# shield_007.net
KiCad netlist of a schematic drawn in EAGLE
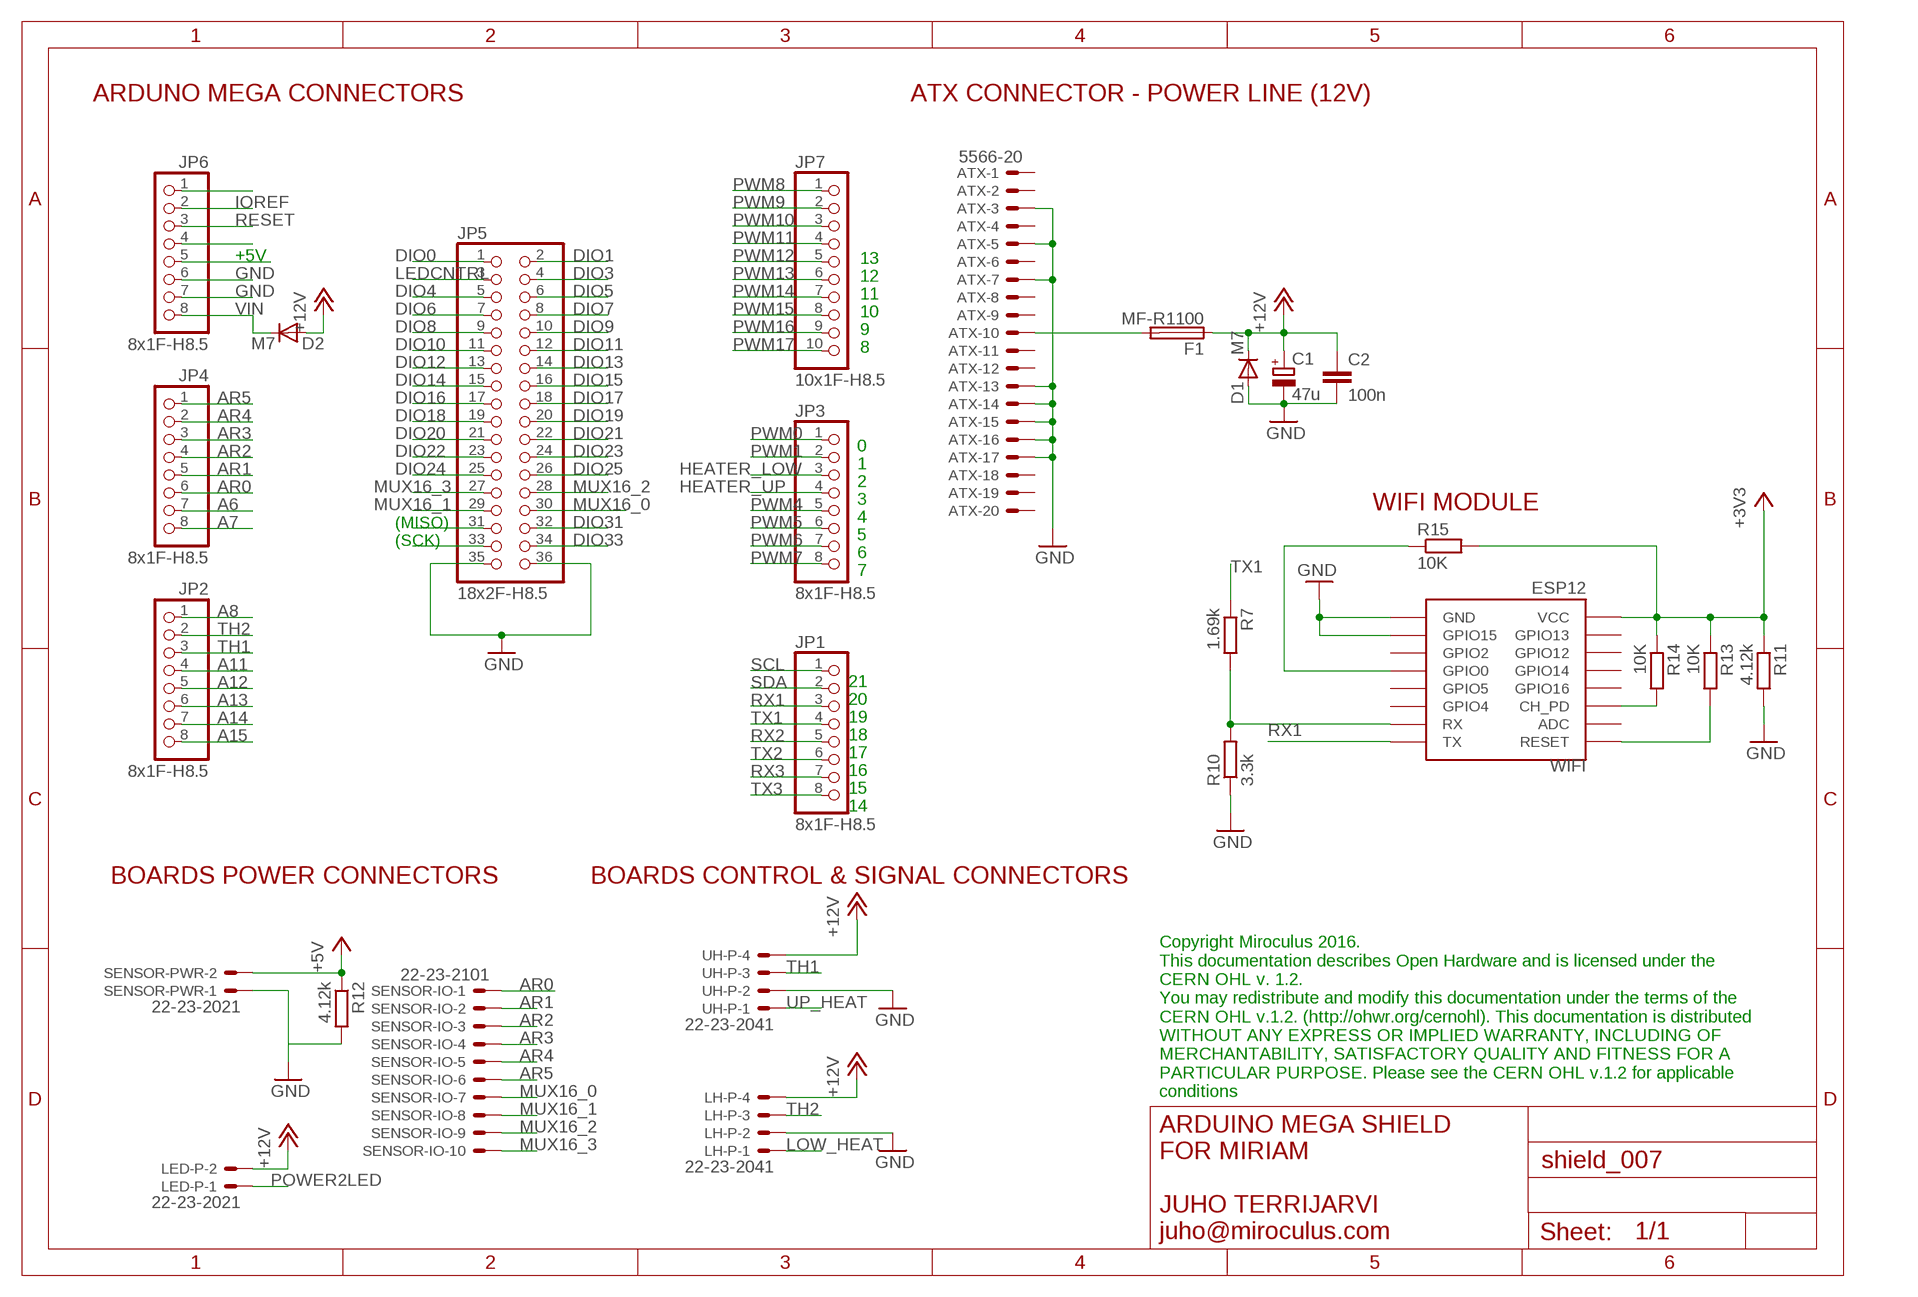
[diagram p0: schematic, sheet 1, part 1 of 2]
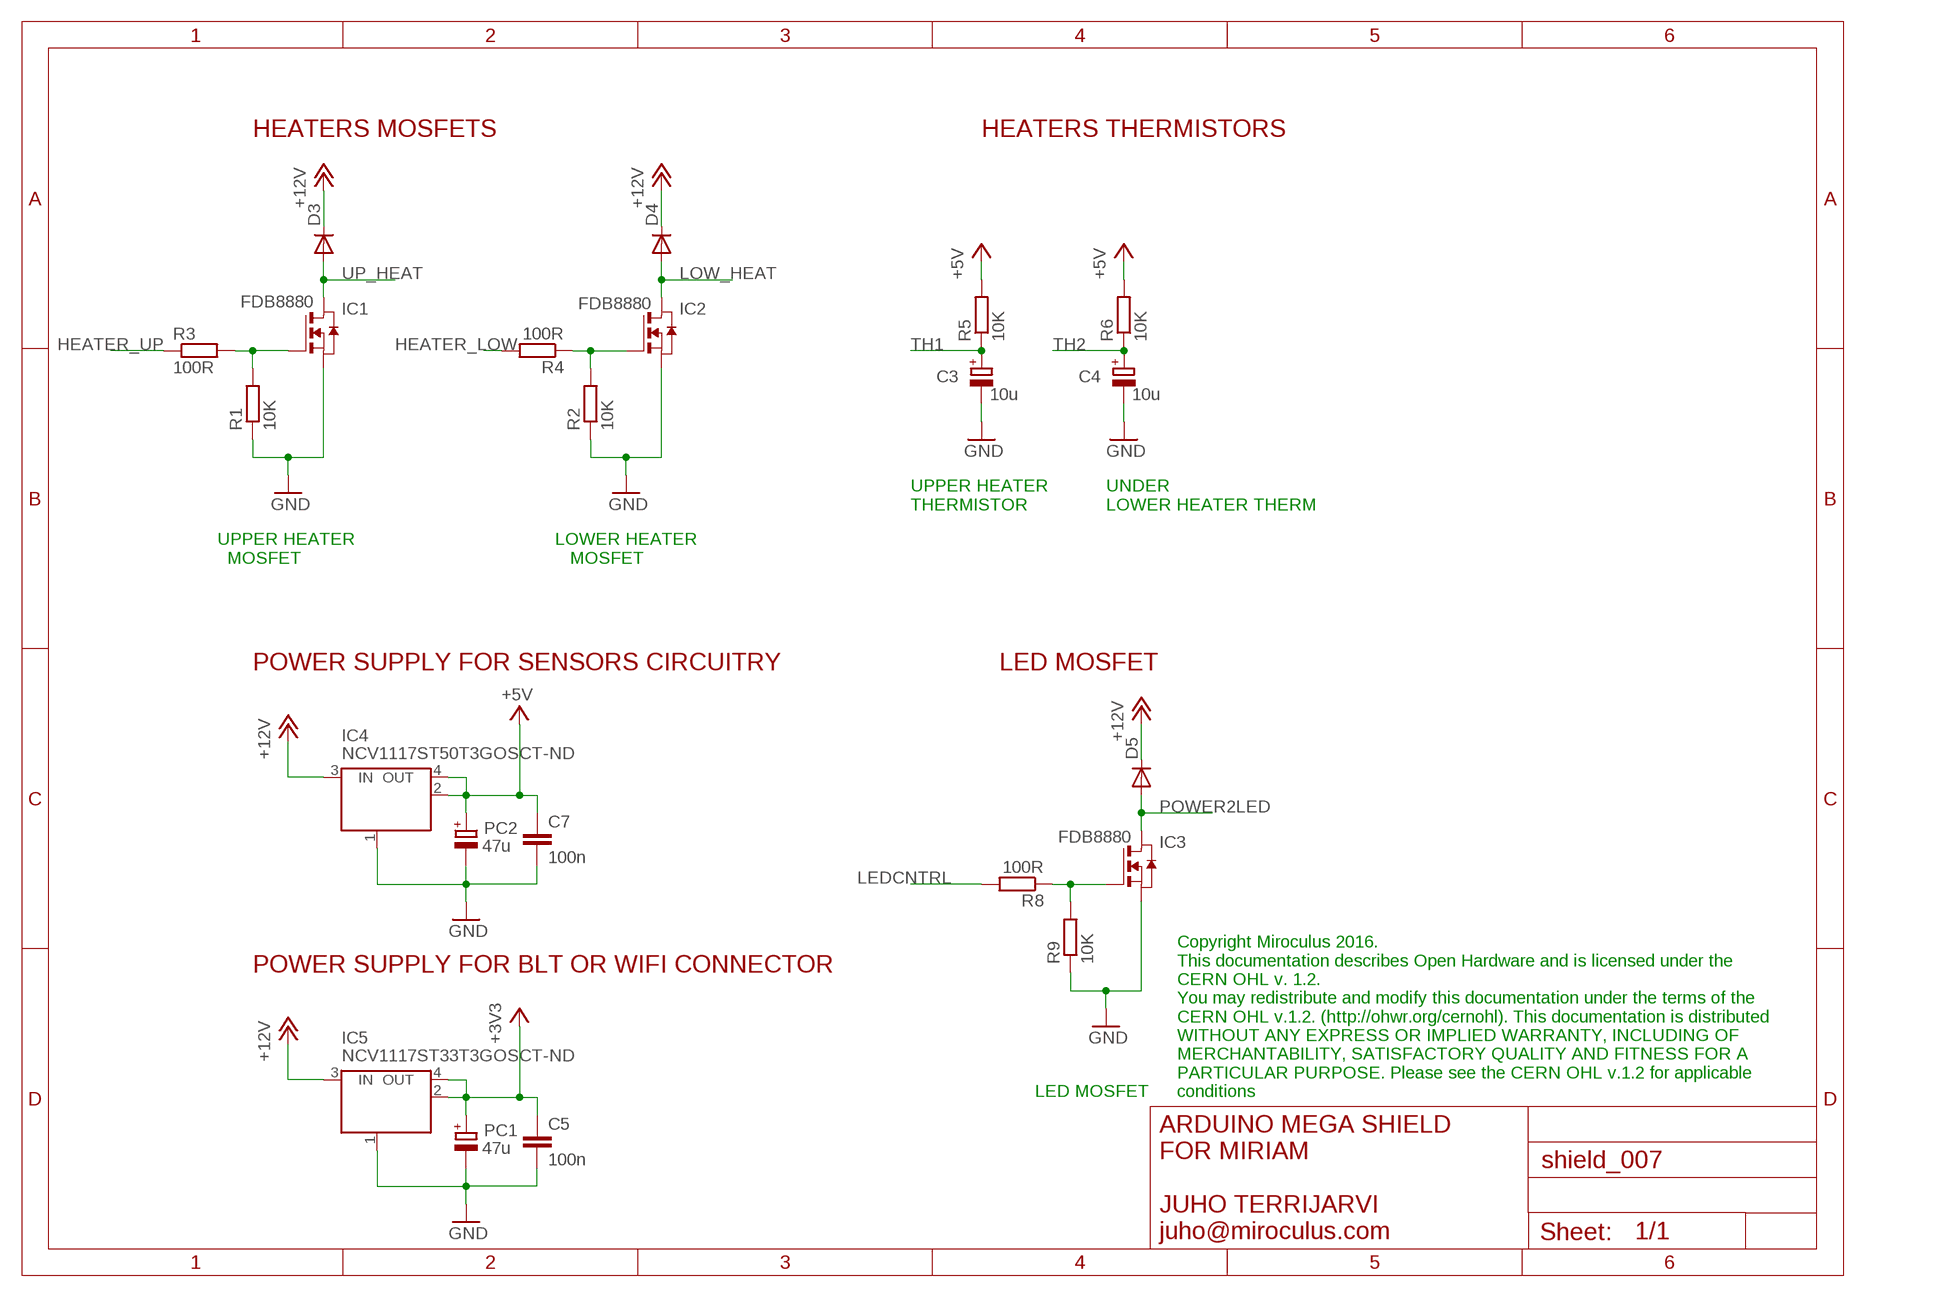
[diagram p1: schematic, sheet 1, part 2 of 2]

(export (version "E")
  (design (tool "Eeschema 10.0.6"))
  (components
    (comp (ref "ATX")
      (value "5566-20")
      (footprint "eagle-import:5566-20")
      (fields (field (name "OC_FARNELL") "9734252"))
      (libsource (lib "eagle-import") (part "5566-20"))
    )
    (comp (ref "C1")
      (value "47u")
      (footprint "eagle-import:PANASONIC_D")
      (libsource (lib "eagle-import") (part "CPOL-EUD"))
    )
    (comp (ref "C2")
      (value "100n")
      (footprint "eagle-import:C0603")
      (libsource (lib "eagle-import") (part "C-EUC0603"))
    )
    (comp (ref "C3")
      (value "10u")
      (footprint "eagle-import:A_3216-18R")
      (libsource (lib "eagle-import") (part "CPOL-EUA/3216-18R"))
    )
    (comp (ref "C4")
      (value "10u")
      (footprint "eagle-import:A_3216-18R")
      (libsource (lib "eagle-import") (part "CPOL-EUA/3216-18R"))
    )
    (comp (ref "C5")
      (value "100n")
      (footprint "eagle-import:C0603")
      (libsource (lib "eagle-import") (part "C-EUC0603"))
    )
    (comp (ref "C7")
      (value "100n")
      (footprint "eagle-import:C0603")
      (libsource (lib "eagle-import") (part "C-EUC0603"))
    )
    (comp (ref "D1")
      (value "M7")
      (footprint "eagle-import:SMB")
      (libsource (lib "eagle-import") (part "DIODE-SMB"))
    )
    (comp (ref "D2")
      (value "M7")
      (footprint "eagle-import:SMB")
      (libsource (lib "eagle-import") (part "DIODE-SMB"))
    )
    (comp (ref "D3")
      (value "RGL34A")
      (footprint "eagle-import:DO-213AA_DIODE")
      (libsource (lib "eagle-import") (part "DO-213_DIODE"))
    )
    (comp (ref "D4")
      (value "RGL34A")
      (footprint "eagle-import:DO-213AA_DIODE")
      (libsource (lib "eagle-import") (part "DO-213_DIODE"))
    )
    (comp (ref "D5")
      (value "RGL34A")
      (footprint "eagle-import:DO-213AA_DIODE")
      (libsource (lib "eagle-import") (part "DO-213_DIODE"))
    )
    (comp (ref "F1")
      (value "MF-R1100")
      (footprint "eagle-import:LITTLEFUSE")
      (libsource (lib "eagle-import") (part "LITTLEFUSE"))
    )
    (comp (ref "IC1")
      (value "FDB8880")
      (footprint "eagle-import:FDB8880")
      (libsource (lib "eagle-import") (part "FDB8880"))
    )
    (comp (ref "IC2")
      (value "FDB8880")
      (footprint "eagle-import:FDB8880")
      (libsource (lib "eagle-import") (part "FDB8880"))
    )
    (comp (ref "IC3")
      (value "FDB8880")
      (footprint "eagle-import:FDB8880")
      (libsource (lib "eagle-import") (part "FDB8880"))
    )
    (comp (ref "IC4")
      (value "NCV1117ST50T3GOSCT-ND")
      (footprint "eagle-import:SOT223")
      (libsource (lib "eagle-import") (part "MC33269ST-3.3T3"))
    )
    (comp (ref "IC5")
      (value "NCV1117ST33T3GOSCT-ND")
      (footprint "eagle-import:SOT223")
      (libsource (lib "eagle-import") (part "MC33269ST-3.3T3"))
    )
    (comp (ref "JP1")
      (value "8x1F-H8.5")
      (footprint "eagle-import:1X08")
      (libsource (lib "eagle-import") (part "PINHD-1X8"))
    )
    (comp (ref "JP2")
      (value "8x1F-H8.5")
      (footprint "eagle-import:1X08")
      (libsource (lib "eagle-import") (part "PINHD-1X8"))
    )
    (comp (ref "JP3")
      (value "8x1F-H8.5")
      (footprint "eagle-import:1X08")
      (libsource (lib "eagle-import") (part "PINHD-1X8"))
    )
    (comp (ref "JP4")
      (value "8x1F-H8.5")
      (footprint "eagle-import:1X08")
      (libsource (lib "eagle-import") (part "PINHD-1X8"))
    )
    (comp (ref "JP5")
      (value "18x2F-H8.5")
      (footprint "eagle-import:2X18")
      (libsource (lib "eagle-import") (part "PINHD-2X18"))
    )
    (comp (ref "JP6")
      (value "8x1F-H8.5")
      (footprint "eagle-import:1X08")
      (libsource (lib "eagle-import") (part "PINHD-1X8"))
    )
    (comp (ref "JP7")
      (value "10x1F-H8.5")
      (footprint "eagle-import:1X10")
      (libsource (lib "eagle-import") (part "PINHD-1X10_ARD"))
    )
    (comp (ref "LED-P")
      (value "22-23-2021")
      (footprint "eagle-import:22-23-2021")
      (fields (field (name "MF") "MOLEX"))
      (libsource (lib "eagle-import") (part "22-23-2021"))
    )
    (comp (ref "LH-P")
      (value "22-23-2041")
      (footprint "eagle-import:22-23-2041")
      (fields (field (name "MF") "MOLEX"))
      (libsource (lib "eagle-import") (part "22-23-2041"))
    )
    (comp (ref "PC1")
      (value "47u")
      (footprint "eagle-import:PANASONIC_D")
      (libsource (lib "eagle-import") (part "CPOL-EUD"))
    )
    (comp (ref "PC2")
      (value "47u")
      (footprint "eagle-import:PANASONIC_D")
      (libsource (lib "eagle-import") (part "CPOL-EUD"))
    )
    (comp (ref "R1")
      (value "10K")
      (footprint "eagle-import:R0603")
      (libsource (lib "eagle-import") (part "R-EU_R0603"))
    )
    (comp (ref "R2")
      (value "10K")
      (footprint "eagle-import:R0603")
      (libsource (lib "eagle-import") (part "R-EU_R0603"))
    )
    (comp (ref "R3")
      (value "100R")
      (footprint "eagle-import:R0603")
      (libsource (lib "eagle-import") (part "R-EU_R0603"))
    )
    (comp (ref "R4")
      (value "100R")
      (footprint "eagle-import:R0603")
      (libsource (lib "eagle-import") (part "R-EU_R0603"))
    )
    (comp (ref "R5")
      (value "10K")
      (footprint "eagle-import:R0603")
      (libsource (lib "eagle-import") (part "R-EU_R0603"))
    )
    (comp (ref "R6")
      (value "10K")
      (footprint "eagle-import:R0603")
      (libsource (lib "eagle-import") (part "R-EU_R0603"))
    )
    (comp (ref "R7")
      (value "1.69k")
      (footprint "eagle-import:R0603")
      (libsource (lib "eagle-import") (part "R-EU_R0603"))
    )
    (comp (ref "R8")
      (value "100R")
      (footprint "eagle-import:R0603")
      (libsource (lib "eagle-import") (part "R-EU_R0603"))
    )
    (comp (ref "R9")
      (value "10K")
      (footprint "eagle-import:R0603")
      (libsource (lib "eagle-import") (part "R-EU_R0603"))
    )
    (comp (ref "R10")
      (value "3.3k")
      (footprint "eagle-import:R0603")
      (libsource (lib "eagle-import") (part "R-EU_R0603"))
    )
    (comp (ref "R11")
      (value "4.12k")
      (footprint "eagle-import:R0603")
      (libsource (lib "eagle-import") (part "R-EU_R0603"))
    )
    (comp (ref "R12")
      (value "4.12k")
      (footprint "eagle-import:R0603")
      (libsource (lib "eagle-import") (part "R-EU_R0603"))
    )
    (comp (ref "R13")
      (value "10K")
      (footprint "eagle-import:R0603")
      (libsource (lib "eagle-import") (part "R-EU_R0603"))
    )
    (comp (ref "R14")
      (value "10K")
      (footprint "eagle-import:R0603")
      (libsource (lib "eagle-import") (part "R-EU_R0603"))
    )
    (comp (ref "R15")
      (value "10K")
      (footprint "eagle-import:R0603")
      (libsource (lib "eagle-import") (part "R-EU_R0603"))
    )
    (comp (ref "SENSOR-IO")
      (value "22-23-2101")
      (footprint "eagle-import:22-23-2101")
      (fields (field (name "MF") "MOLEX"))
      (libsource (lib "eagle-import") (part "22-23-2101"))
    )
    (comp (ref "SENSOR-PWR")
      (value "22-23-2021")
      (footprint "eagle-import:22-23-2021")
      (fields (field (name "MF") "MOLEX"))
      (libsource (lib "eagle-import") (part "22-23-2021"))
    )
    (comp (ref "UH-P")
      (value "22-23-2041")
      (footprint "eagle-import:22-23-2041")
      (fields (field (name "MF") "MOLEX"))
      (libsource (lib "eagle-import") (part "22-23-2041"))
    )
    (comp (ref "WIFI")
      (value "ESP12")
      (footprint "eagle-import:ESP12")
      (libsource (lib "eagle-import") (part "ESP12"))
    )
  )
  (nets
    (net (code "1") (name "+3V3") (class "Default")
      (node (ref "C5") (pin "1") (pinfunction "1_1") (pintype "passive"))
      (node (ref "IC5") (pin "2") (pinfunction "OUT_2") (pintype "passive"))
      (node (ref "IC5") (pin "4") (pinfunction "OUT_4") (pintype "passive"))
      (node (ref "PC1") (pin "+") (pinfunction "+_+") (pintype "passive"))
      (node (ref "R11") (pin "1") (pinfunction "1_1") (pintype "passive"))
      (node (ref "R13") (pin "1") (pinfunction "1_1") (pintype "passive"))
      (node (ref "R14") (pin "1") (pinfunction "1_1") (pintype "passive"))
      (node (ref "R15") (pin "2") (pinfunction "2_2") (pintype "passive"))
      (node (ref "WIFI") (pin "VCC") (pinfunction "VCC_VCC") (pintype "bidirectional"))
    )
    (net (code "2") (name "+5V") (class "Default")
      (node (ref "C7") (pin "1") (pinfunction "1_1") (pintype "passive"))
      (node (ref "IC4") (pin "2") (pinfunction "OUT_2") (pintype "passive"))
      (node (ref "IC4") (pin "4") (pinfunction "OUT_4") (pintype "passive"))
      (node (ref "PC2") (pin "+") (pinfunction "+_+") (pintype "passive"))
      (node (ref "R12") (pin "1") (pinfunction "1_1") (pintype "passive"))
      (node (ref "R5") (pin "2") (pinfunction "2_2") (pintype "passive"))
      (node (ref "R6") (pin "2") (pinfunction "2_2") (pintype "passive"))
      (node (ref "SENSOR-PWR") (pin "2") (pinfunction "S_2") (pintype "passive"))
    )
    (net (code "3") (name "+12V") (class "Default")
      (node (ref "C1") (pin "+") (pinfunction "+_+") (pintype "passive"))
      (node (ref "C2") (pin "1") (pinfunction "1_1") (pintype "passive"))
      (node (ref "D1") (pin "C") (pinfunction "C_C") (pintype "passive"))
      (node (ref "D2") (pin "A") (pinfunction "A_A") (pintype "passive"))
      (node (ref "D3") (pin "P$2") (pinfunction "C_P$2") (pintype "passive"))
      (node (ref "D4") (pin "P$2") (pinfunction "C_P$2") (pintype "passive"))
      (node (ref "D5") (pin "P$2") (pinfunction "C_P$2") (pintype "passive"))
      (node (ref "F1") (pin "1") (pinfunction "1_1") (pintype "passive"))
      (node (ref "IC4") (pin "3") (pinfunction "IN_3") (pintype "input"))
      (node (ref "IC5") (pin "3") (pinfunction "IN_3") (pintype "input"))
      (node (ref "LED-P") (pin "2") (pinfunction "S_2") (pintype "passive"))
      (node (ref "LH-P") (pin "4") (pinfunction "S_4") (pintype "passive"))
      (node (ref "UH-P") (pin "4") (pinfunction "S_4") (pintype "passive"))
    )
    (net (code "4") (name "/A6") (class "Default")
      (node (ref "JP4") (pin "7") (pinfunction "7_7") (pintype "passive"))
    )
    (net (code "5") (name "/A7") (class "Default")
      (node (ref "JP4") (pin "8") (pinfunction "8_8") (pintype "passive"))
    )
    (net (code "6") (name "/A8") (class "Default")
      (node (ref "JP2") (pin "1") (pinfunction "1_1") (pintype "passive"))
    )
    (net (code "7") (name "/A11") (class "Default")
      (node (ref "JP2") (pin "4") (pinfunction "4_4") (pintype "passive"))
    )
    (net (code "8") (name "/A12") (class "Default")
      (node (ref "JP2") (pin "5") (pinfunction "5_5") (pintype "passive"))
    )
    (net (code "9") (name "/A13") (class "Default")
      (node (ref "JP2") (pin "6") (pinfunction "6_6") (pintype "passive"))
    )
    (net (code "10") (name "/A14") (class "Default")
      (node (ref "JP2") (pin "7") (pinfunction "7_7") (pintype "passive"))
    )
    (net (code "11") (name "/A15") (class "Default")
      (node (ref "JP2") (pin "8") (pinfunction "8_8") (pintype "passive"))
    )
    (net (code "12") (name "/AR0") (class "Default")
      (node (ref "JP4") (pin "6") (pinfunction "6_6") (pintype "passive"))
      (node (ref "SENSOR-IO") (pin "1") (pinfunction "S_1") (pintype "passive"))
    )
    (net (code "13") (name "/AR1") (class "Default")
      (node (ref "JP4") (pin "5") (pinfunction "5_5") (pintype "passive"))
      (node (ref "SENSOR-IO") (pin "2") (pinfunction "S_2") (pintype "passive"))
    )
    (net (code "14") (name "/AR2") (class "Default")
      (node (ref "JP4") (pin "4") (pinfunction "4_4") (pintype "passive"))
      (node (ref "SENSOR-IO") (pin "3") (pinfunction "S_3") (pintype "passive"))
    )
    (net (code "15") (name "/AR3") (class "Default")
      (node (ref "JP4") (pin "3") (pinfunction "3_3") (pintype "passive"))
      (node (ref "SENSOR-IO") (pin "4") (pinfunction "S_4") (pintype "passive"))
    )
    (net (code "16") (name "/AR4") (class "Default")
      (node (ref "JP4") (pin "2") (pinfunction "2_2") (pintype "passive"))
      (node (ref "SENSOR-IO") (pin "5") (pinfunction "S_5") (pintype "passive"))
    )
    (net (code "17") (name "/AR5") (class "Default")
      (node (ref "JP4") (pin "1") (pinfunction "1_1") (pintype "passive"))
      (node (ref "SENSOR-IO") (pin "6") (pinfunction "S_6") (pintype "passive"))
    )
    (net (code "18") (name "/DIO0") (class "Default")
      (node (ref "JP5") (pin "1") (pinfunction "1_1") (pintype "passive"))
    )
    (net (code "19") (name "/DIO1") (class "Default")
      (node (ref "JP5") (pin "2") (pinfunction "2_2") (pintype "passive"))
    )
    (net (code "20") (name "/DIO3") (class "Default")
      (node (ref "JP5") (pin "4") (pinfunction "4_4") (pintype "passive"))
    )
    (net (code "21") (name "/DIO4") (class "Default")
      (node (ref "JP5") (pin "5") (pinfunction "5_5") (pintype "passive"))
    )
    (net (code "22") (name "/DIO5") (class "Default")
      (node (ref "JP5") (pin "6") (pinfunction "6_6") (pintype "passive"))
    )
    (net (code "23") (name "/DIO6") (class "Default")
      (node (ref "JP5") (pin "7") (pinfunction "7_7") (pintype "passive"))
    )
    (net (code "24") (name "/DIO7") (class "Default")
      (node (ref "JP5") (pin "8") (pinfunction "8_8") (pintype "passive"))
    )
    (net (code "25") (name "/DIO8") (class "Default")
      (node (ref "JP5") (pin "9") (pinfunction "9_9") (pintype "passive"))
    )
    (net (code "26") (name "/DIO9") (class "Default")
      (node (ref "JP5") (pin "10") (pinfunction "10_10") (pintype "passive"))
    )
    (net (code "27") (name "/DIO10") (class "Default")
      (node (ref "JP5") (pin "11") (pinfunction "11_11") (pintype "passive"))
    )
    (net (code "28") (name "/DIO11") (class "Default")
      (node (ref "JP5") (pin "12") (pinfunction "12_12") (pintype "passive"))
    )
    (net (code "29") (name "/DIO12") (class "Default")
      (node (ref "JP5") (pin "13") (pinfunction "13_13") (pintype "passive"))
    )
    (net (code "30") (name "/DIO13") (class "Default")
      (node (ref "JP5") (pin "14") (pinfunction "14_14") (pintype "passive"))
    )
    (net (code "31") (name "/DIO14") (class "Default")
      (node (ref "JP5") (pin "15") (pinfunction "15_15") (pintype "passive"))
    )
    (net (code "32") (name "/DIO15") (class "Default")
      (node (ref "JP5") (pin "16") (pinfunction "16_16") (pintype "passive"))
    )
    (net (code "33") (name "/DIO16") (class "Default")
      (node (ref "JP5") (pin "17") (pinfunction "17_17") (pintype "passive"))
    )
    (net (code "34") (name "/DIO17") (class "Default")
      (node (ref "JP5") (pin "18") (pinfunction "18_18") (pintype "passive"))
    )
    (net (code "35") (name "/DIO18") (class "Default")
      (node (ref "JP5") (pin "19") (pinfunction "19_19") (pintype "passive"))
    )
    (net (code "36") (name "/DIO19") (class "Default")
      (node (ref "JP5") (pin "20") (pinfunction "20_20") (pintype "passive"))
    )
    (net (code "37") (name "/DIO20") (class "Default")
      (node (ref "JP5") (pin "21") (pinfunction "21_21") (pintype "passive"))
    )
    (net (code "38") (name "/DIO21") (class "Default")
      (node (ref "JP5") (pin "22") (pinfunction "22_22") (pintype "passive"))
    )
    (net (code "39") (name "/DIO22") (class "Default")
      (node (ref "JP5") (pin "23") (pinfunction "23_23") (pintype "passive"))
    )
    (net (code "40") (name "/DIO23") (class "Default")
      (node (ref "JP5") (pin "24") (pinfunction "24_24") (pintype "passive"))
    )
    (net (code "41") (name "/DIO24") (class "Default")
      (node (ref "JP5") (pin "25") (pinfunction "25_25") (pintype "passive"))
    )
    (net (code "42") (name "/DIO25") (class "Default")
      (node (ref "JP5") (pin "26") (pinfunction "26_26") (pintype "passive"))
    )
    (net (code "43") (name "/DIO31") (class "Default")
      (node (ref "JP5") (pin "32") (pinfunction "32_32") (pintype "passive"))
    )
    (net (code "44") (name "/DIO33") (class "Default")
      (node (ref "JP5") (pin "34") (pinfunction "34_34") (pintype "passive"))
    )
    (net (code "45") (name "/HEATER_LOW") (class "Default")
      (node (ref "JP3") (pin "3") (pinfunction "3_3") (pintype "passive"))
      (node (ref "R4") (pin "2") (pinfunction "2_2") (pintype "passive"))
    )
    (net (code "46") (name "/HEATER_UP") (class "Default")
      (node (ref "JP3") (pin "4") (pinfunction "4_4") (pintype "passive"))
      (node (ref "R3") (pin "1") (pinfunction "1_1") (pintype "passive"))
    )
    (net (code "47") (name "/IOREF") (class "Default")
      (node (ref "JP6") (pin "2") (pinfunction "2_2") (pintype "passive"))
    )
    (net (code "48") (name "/LEDCNTRL") (class "Default")
      (node (ref "JP5") (pin "3") (pinfunction "3_3") (pintype "passive"))
      (node (ref "R8") (pin "2") (pinfunction "2_2") (pintype "passive"))
    )
    (net (code "49") (name "/LOW_HEAT") (class "Default")
      (node (ref "D4") (pin "P$1") (pinfunction "A_P$1") (pintype "passive"))
      (node (ref "IC2") (pin "2") (pinfunction "D_2") (pintype "passive"))
      (node (ref "LH-P") (pin "1") (pinfunction "S_1") (pintype "passive"))
    )
    (net (code "50") (name "/MUX16_0") (class "Default")
      (node (ref "JP5") (pin "30") (pinfunction "30_30") (pintype "passive"))
      (node (ref "SENSOR-IO") (pin "7") (pinfunction "S_7") (pintype "passive"))
    )
    (net (code "51") (name "/MUX16_1") (class "Default")
      (node (ref "JP5") (pin "29") (pinfunction "29_29") (pintype "passive"))
      (node (ref "SENSOR-IO") (pin "8") (pinfunction "S_8") (pintype "passive"))
    )
    (net (code "52") (name "/MUX16_2") (class "Default")
      (node (ref "JP5") (pin "28") (pinfunction "28_28") (pintype "passive"))
      (node (ref "SENSOR-IO") (pin "9") (pinfunction "S_9") (pintype "passive"))
    )
    (net (code "53") (name "/MUX16_3") (class "Default")
      (node (ref "JP5") (pin "27") (pinfunction "27_27") (pintype "passive"))
      (node (ref "SENSOR-IO") (pin "10") (pinfunction "S_10") (pintype "passive"))
    )
    (net (code "54") (name "/POWER2LED") (class "Default")
      (node (ref "D5") (pin "P$1") (pinfunction "A_P$1") (pintype "passive"))
      (node (ref "IC3") (pin "2") (pinfunction "D_2") (pintype "passive"))
      (node (ref "LED-P") (pin "1") (pinfunction "S_1") (pintype "passive"))
    )
    (net (code "55") (name "/PWM0") (class "Default")
      (node (ref "JP3") (pin "1") (pinfunction "1_1") (pintype "passive"))
    )
    (net (code "56") (name "/PWM1") (class "Default")
      (node (ref "JP3") (pin "2") (pinfunction "2_2") (pintype "passive"))
    )
    (net (code "57") (name "/PWM4") (class "Default")
      (node (ref "JP3") (pin "5") (pinfunction "5_5") (pintype "passive"))
    )
    (net (code "58") (name "/PWM5") (class "Default")
      (node (ref "JP3") (pin "6") (pinfunction "6_6") (pintype "passive"))
    )
    (net (code "59") (name "/PWM6") (class "Default")
      (node (ref "JP3") (pin "7") (pinfunction "7_7") (pintype "passive"))
    )
    (net (code "60") (name "/PWM7") (class "Default")
      (node (ref "JP3") (pin "8") (pinfunction "8_8") (pintype "passive"))
    )
    (net (code "61") (name "/PWM8") (class "Default")
      (node (ref "JP7") (pin "1") (pinfunction "1_1") (pintype "passive"))
    )
    (net (code "62") (name "/PWM9") (class "Default")
      (node (ref "JP7") (pin "2") (pinfunction "2_2") (pintype "passive"))
    )
    (net (code "63") (name "/PWM10") (class "Default")
      (node (ref "JP7") (pin "3") (pinfunction "3_3") (pintype "passive"))
    )
    (net (code "64") (name "/PWM11") (class "Default")
      (node (ref "JP7") (pin "4") (pinfunction "4_4") (pintype "passive"))
    )
    (net (code "65") (name "/PWM12") (class "Default")
      (node (ref "JP7") (pin "5") (pinfunction "5_5") (pintype "passive"))
    )
    (net (code "66") (name "/PWM13") (class "Default")
      (node (ref "JP7") (pin "6") (pinfunction "6_6") (pintype "passive"))
    )
    (net (code "67") (name "/PWM14") (class "Default")
      (node (ref "JP7") (pin "7") (pinfunction "7_7") (pintype "passive"))
    )
    (net (code "68") (name "/PWM15") (class "Default")
      (node (ref "JP7") (pin "8") (pinfunction "8_8") (pintype "passive"))
    )
    (net (code "69") (name "/PWM16") (class "Default")
      (node (ref "JP7") (pin "9") (pinfunction "9_9") (pintype "passive"))
    )
    (net (code "70") (name "/PWM17") (class "Default")
      (node (ref "JP7") (pin "10") (pinfunction "10_10") (pintype "passive"))
    )
    (net (code "71") (name "/RESET") (class "Default")
      (node (ref "JP6") (pin "3") (pinfunction "3_3") (pintype "passive"))
    )
    (net (code "72") (name "/RX1") (class "Default")
      (node (ref "JP1") (pin "3") (pinfunction "3_3") (pintype "passive"))
      (node (ref "WIFI") (pin "TX") (pinfunction "TX_TX") (pintype "bidirectional"))
    )
    (net (code "73") (name "/RX2") (class "Default")
      (node (ref "JP1") (pin "5") (pinfunction "5_5") (pintype "passive"))
    )
    (net (code "74") (name "/RX3") (class "Default")
      (node (ref "JP1") (pin "7") (pinfunction "7_7") (pintype "passive"))
    )
    (net (code "75") (name "/SCL") (class "Default")
      (node (ref "JP1") (pin "1") (pinfunction "1_1") (pintype "passive"))
    )
    (net (code "76") (name "/SDA") (class "Default")
      (node (ref "JP1") (pin "2") (pinfunction "2_2") (pintype "passive"))
    )
    (net (code "77") (name "/TH1") (class "Default")
      (node (ref "C3") (pin "+") (pinfunction "+_+") (pintype "passive"))
      (node (ref "JP2") (pin "3") (pinfunction "3_3") (pintype "passive"))
      (node (ref "R5") (pin "1") (pinfunction "1_1") (pintype "passive"))
      (node (ref "UH-P") (pin "3") (pinfunction "S_3") (pintype "passive"))
    )
    (net (code "78") (name "/TH2") (class "Default")
      (node (ref "C4") (pin "+") (pinfunction "+_+") (pintype "passive"))
      (node (ref "JP2") (pin "2") (pinfunction "2_2") (pintype "passive"))
      (node (ref "LH-P") (pin "3") (pinfunction "S_3") (pintype "passive"))
      (node (ref "R6") (pin "1") (pinfunction "1_1") (pintype "passive"))
    )
    (net (code "79") (name "/TX1") (class "Default")
      (node (ref "JP1") (pin "4") (pinfunction "4_4") (pintype "passive"))
      (node (ref "R7") (pin "1") (pinfunction "1_1") (pintype "passive"))
    )
    (net (code "80") (name "/TX2") (class "Default")
      (node (ref "JP1") (pin "6") (pinfunction "6_6") (pintype "passive"))
    )
    (net (code "81") (name "/TX3") (class "Default")
      (node (ref "JP1") (pin "8") (pinfunction "8_8") (pintype "passive"))
    )
    (net (code "82") (name "/UP_HEAT") (class "Default")
      (node (ref "D3") (pin "P$1") (pinfunction "A_P$1") (pintype "passive"))
      (node (ref "IC1") (pin "2") (pinfunction "D_2") (pintype "passive"))
      (node (ref "UH-P") (pin "1") (pinfunction "S_1") (pintype "passive"))
    )
    (net (code "83") (name "/VIN") (class "Default")
      (node (ref "D2") (pin "C") (pinfunction "C_C") (pintype "passive"))
      (node (ref "JP6") (pin "8") (pinfunction "8_8") (pintype "passive"))
    )
    (net (code "84") (name "GND") (class "Default")
      (node (ref "ATX") (pin "13") (pinfunction "S_13") (pintype "passive"))
      (node (ref "ATX") (pin "14") (pinfunction "S_14") (pintype "passive"))
      (node (ref "ATX") (pin "15") (pinfunction "S_15") (pintype "passive"))
      (node (ref "ATX") (pin "16") (pinfunction "S_16") (pintype "passive"))
      (node (ref "ATX") (pin "17") (pinfunction "S_17") (pintype "passive"))
      (node (ref "ATX") (pin "3") (pinfunction "S_3") (pintype "passive"))
      (node (ref "ATX") (pin "5") (pinfunction "S_5") (pintype "passive"))
      (node (ref "ATX") (pin "7") (pinfunction "S_7") (pintype "passive"))
      (node (ref "C1") (pin "-") (pinfunction "-_-") (pintype "passive"))
      (node (ref "C2") (pin "2") (pinfunction "2_2") (pintype "passive"))
      (node (ref "C3") (pin "-") (pinfunction "-_-") (pintype "passive"))
      (node (ref "C4") (pin "-") (pinfunction "-_-") (pintype "passive"))
      (node (ref "C5") (pin "2") (pinfunction "2_2") (pintype "passive"))
      (node (ref "C7") (pin "2") (pinfunction "2_2") (pintype "passive"))
      (node (ref "D1") (pin "A") (pinfunction "A_A") (pintype "passive"))
      (node (ref "IC1") (pin "3") (pinfunction "S_3") (pintype "passive"))
      (node (ref "IC2") (pin "3") (pinfunction "S_3") (pintype "passive"))
      (node (ref "IC3") (pin "3") (pinfunction "S_3") (pintype "passive"))
      (node (ref "IC4") (pin "1") (pinfunction "GND/ADJ_1") (pintype "input"))
      (node (ref "IC5") (pin "1") (pinfunction "GND/ADJ_1") (pintype "input"))
      (node (ref "JP5") (pin "35") (pinfunction "35_35") (pintype "passive"))
      (node (ref "JP5") (pin "36") (pinfunction "36_36") (pintype "passive"))
      (node (ref "JP6") (pin "6") (pinfunction "6_6") (pintype "passive"))
      (node (ref "JP6") (pin "7") (pinfunction "7_7") (pintype "passive"))
      (node (ref "LH-P") (pin "2") (pinfunction "S_2") (pintype "passive"))
      (node (ref "PC1") (pin "-") (pinfunction "-_-") (pintype "passive"))
      (node (ref "PC2") (pin "-") (pinfunction "-_-") (pintype "passive"))
      (node (ref "R1") (pin "1") (pinfunction "1_1") (pintype "passive"))
      (node (ref "R10") (pin "1") (pinfunction "1_1") (pintype "passive"))
      (node (ref "R11") (pin "2") (pinfunction "2_2") (pintype "passive"))
      (node (ref "R12") (pin "2") (pinfunction "2_2") (pintype "passive"))
      (node (ref "R2") (pin "1") (pinfunction "1_1") (pintype "passive"))
      (node (ref "R9") (pin "1") (pinfunction "1_1") (pintype "passive"))
      (node (ref "SENSOR-PWR") (pin "1") (pinfunction "S_1") (pintype "passive"))
      (node (ref "UH-P") (pin "2") (pinfunction "S_2") (pintype "passive"))
      (node (ref "WIFI") (pin "GND") (pinfunction "GND_GND") (pintype "bidirectional"))
      (node (ref "WIFI") (pin "GPIO15") (pinfunction "GPIO15_GPIO15") (pintype "bidirectional"))
    )
    (net (code "85") (name "Net-(ATXB-S)") (class "Default")
      (node (ref "ATX") (pin "10") (pinfunction "S_10") (pintype "passive"))
      (node (ref "F1") (pin "2") (pinfunction "2_2") (pintype "passive"))
    )
    (net (code "86") (name "Net-(IC1-G)") (class "Default")
      (node (ref "IC1") (pin "1") (pinfunction "G_1") (pintype "passive"))
      (node (ref "R1") (pin "2") (pinfunction "2_2") (pintype "passive"))
      (node (ref "R3") (pin "2") (pinfunction "2_2") (pintype "passive"))
    )
    (net (code "87") (name "Net-(IC2-G)") (class "Default")
      (node (ref "IC2") (pin "1") (pinfunction "G_1") (pintype "passive"))
      (node (ref "R2") (pin "2") (pinfunction "2_2") (pintype "passive"))
      (node (ref "R4") (pin "1") (pinfunction "1_1") (pintype "passive"))
    )
    (net (code "88") (name "Net-(IC3-G)") (class "Default")
      (node (ref "IC3") (pin "1") (pinfunction "G_1") (pintype "passive"))
      (node (ref "R8") (pin "1") (pinfunction "1_1") (pintype "passive"))
      (node (ref "R9") (pin "2") (pinfunction "2_2") (pintype "passive"))
    )
    (net (code "89") (name "Net-(R10-Pad2)") (class "Default")
      (node (ref "R10") (pin "2") (pinfunction "2_2") (pintype "passive"))
      (node (ref "R7") (pin "2") (pinfunction "2_2") (pintype "passive"))
      (node (ref "WIFI") (pin "RX") (pinfunction "RX_RX") (pintype "bidirectional"))
    )
    (net (code "90") (name "Net-(R13-Pad2)") (class "Default")
      (node (ref "R13") (pin "2") (pinfunction "2_2") (pintype "passive"))
      (node (ref "WIFI") (pin "RESET") (pinfunction "RESET_RESET") (pintype "bidirectional"))
    )
    (net (code "91") (name "Net-(R14-Pad2)") (class "Default")
      (node (ref "R14") (pin "2") (pinfunction "2_2") (pintype "passive"))
      (node (ref "WIFI") (pin "CH_PD") (pinfunction "CH_PD_CH_PD") (pintype "bidirectional"))
    )
    (net (code "92") (name "Net-(R15-Pad1)") (class "Default")
      (node (ref "R15") (pin "1") (pinfunction "1_1") (pintype "passive"))
      (node (ref "WIFI") (pin "GPIO0") (pinfunction "GPIO0_GPIO0") (pintype "bidirectional"))
    )
    (net (code "93") (name "unconnected-(ATXA-S-Pad1)") (class "Default")
      (node (ref "ATX") (pin "1") (pinfunction "S_1") (pintype "passive"))
    )
    (net (code "94") (name "unconnected-(ATXC-S-Pad11)") (class "Default")
      (node (ref "ATX") (pin "11") (pinfunction "S_11") (pintype "passive"))
    )
    (net (code "95") (name "unconnected-(ATXD-S-Pad12)") (class "Default")
      (node (ref "ATX") (pin "12") (pinfunction "S_12") (pintype "passive"))
    )
    (net (code "96") (name "unconnected-(ATXJ-S-Pad18)") (class "Default")
      (node (ref "ATX") (pin "18") (pinfunction "S_18") (pintype "passive"))
    )
    (net (code "97") (name "unconnected-(ATXK-S-Pad19)") (class "Default")
      (node (ref "ATX") (pin "19") (pinfunction "S_19") (pintype "passive"))
    )
    (net (code "98") (name "unconnected-(ATXL-S-Pad2)") (class "Default")
      (node (ref "ATX") (pin "2") (pinfunction "S_2") (pintype "passive"))
    )
    (net (code "99") (name "unconnected-(ATXM-S-Pad20)") (class "Default")
      (node (ref "ATX") (pin "20") (pinfunction "S_20") (pintype "passive"))
    )
    (net (code "100") (name "unconnected-(ATXO-S-Pad4)") (class "Default")
      (node (ref "ATX") (pin "4") (pinfunction "S_4") (pintype "passive"))
    )
    (net (code "101") (name "unconnected-(ATXQ-S-Pad6)") (class "Default")
      (node (ref "ATX") (pin "6") (pinfunction "S_6") (pintype "passive"))
    )
    (net (code "102") (name "unconnected-(ATXS-S-Pad8)") (class "Default")
      (node (ref "ATX") (pin "8") (pinfunction "S_8") (pintype "passive"))
    )
    (net (code "103") (name "unconnected-(ATXT-S-Pad9)") (class "Default")
      (node (ref "ATX") (pin "9") (pinfunction "S_9") (pintype "passive"))
    )
    (net (code "104") (name "unconnected-(JP5-Pad31)") (class "Default")
      (node (ref "JP5") (pin "31") (pinfunction "31_31") (pintype "passive"))
    )
    (net (code "105") (name "unconnected-(JP5-Pad33)") (class "Default")
      (node (ref "JP5") (pin "33") (pinfunction "33_33") (pintype "passive"))
    )
    (net (code "106") (name "unconnected-(JP6-Pad1)") (class "Default")
      (node (ref "JP6") (pin "1") (pinfunction "1_1") (pintype "passive"))
    )
    (net (code "107") (name "unconnected-(JP6-Pad4)") (class "Default")
      (node (ref "JP6") (pin "4") (pinfunction "4_4") (pintype "passive"))
    )
    (net (code "108") (name "unconnected-(JP6-Pad5)") (class "Default")
      (node (ref "JP6") (pin "5") (pinfunction "5_5") (pintype "passive"))
    )
    (net (code "109") (name "unconnected-(WIFI-PadADC)") (class "Default")
      (node (ref "WIFI") (pin "ADC") (pinfunction "ADC_ADC") (pintype "bidirectional"))
    )
    (net (code "110") (name "unconnected-(WIFI-PadGPIO2)") (class "Default")
      (node (ref "WIFI") (pin "GPIO2") (pinfunction "GPIO2_GPIO2") (pintype "bidirectional"))
    )
    (net (code "111") (name "unconnected-(WIFI-PadGPIO4)") (class "Default")
      (node (ref "WIFI") (pin "GPIO4") (pinfunction "GPIO4_GPIO4") (pintype "bidirectional"))
    )
    (net (code "112") (name "unconnected-(WIFI-PadGPIO5)") (class "Default")
      (node (ref "WIFI") (pin "GPIO5") (pinfunction "GPIO5_GPIO5") (pintype "bidirectional"))
    )
    (net (code "113") (name "unconnected-(WIFI-PadGPIO12)") (class "Default")
      (node (ref "WIFI") (pin "GPIO12") (pinfunction "GPIO12_GPIO12") (pintype "bidirectional"))
    )
    (net (code "114") (name "unconnected-(WIFI-PadGPIO13)") (class "Default")
      (node (ref "WIFI") (pin "GPIO13") (pinfunction "GPIO13_GPIO13") (pintype "bidirectional"))
    )
    (net (code "115") (name "unconnected-(WIFI-PadGPIO14)") (class "Default")
      (node (ref "WIFI") (pin "GPIO14") (pinfunction "GPIO14_GPIO14") (pintype "bidirectional"))
    )
    (net (code "116") (name "unconnected-(WIFI-PadGPIO16)") (class "Default")
      (node (ref "WIFI") (pin "GPIO16") (pinfunction "GPIO16_GPIO16") (pintype "bidirectional"))
    )
  )
)
